# triangle.net
KiCad netlist of a schematic drawn in EAGLE
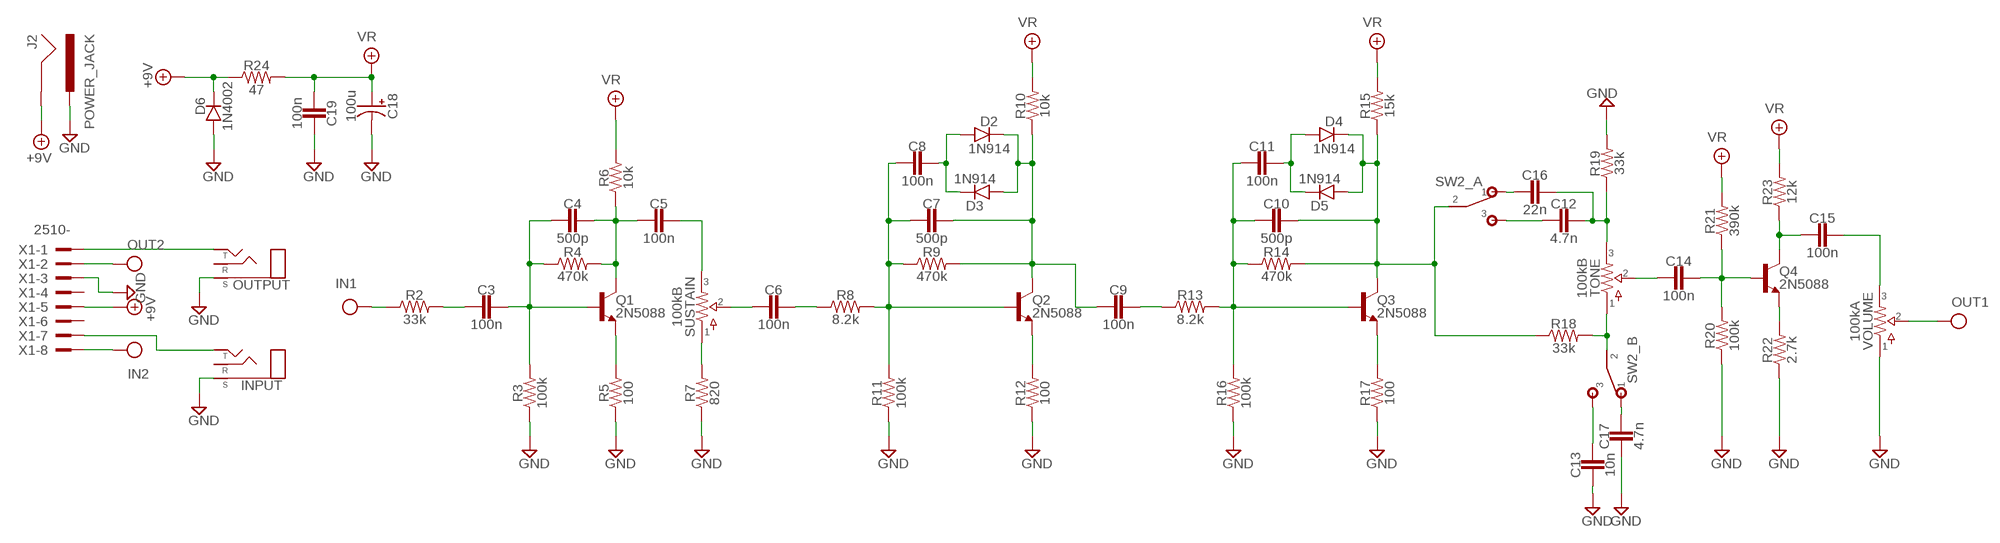
[diagram p0: schematic, sheet 1]

(export (version "E")
  (design (tool "Eeschema 10.0.6"))
  (components
    (comp (ref "C3")
      (value "100n")
      (footprint "eagle-import:BOX_SMALL")
      (libsource (lib "eagle-import") (part "CER/FILMBOX.1"))
    )
    (comp (ref "C4")
      (value "500p")
      (footprint "eagle-import:050X030_025_2")
      (libsource (lib "eagle-import") (part "CER/FILM2"))
    )
    (comp (ref "C5")
      (value "100n")
      (footprint "eagle-import:BOX_SMALL")
      (libsource (lib "eagle-import") (part "CER/FILMBOX.1"))
    )
    (comp (ref "C6")
      (value "100n")
      (footprint "eagle-import:BOX_SMALL")
      (libsource (lib "eagle-import") (part "CER/FILMBOX.1"))
    )
    (comp (ref "C7")
      (value "500p")
      (footprint "eagle-import:050X030_025_2")
      (libsource (lib "eagle-import") (part "CER/FILM2"))
    )
    (comp (ref "C8")
      (value "100n")
      (footprint "eagle-import:BOX_SMALL")
      (libsource (lib "eagle-import") (part "CER/FILMBOX.1"))
    )
    (comp (ref "C9")
      (value "100n")
      (footprint "eagle-import:BOX_SMALL")
      (libsource (lib "eagle-import") (part "CER/FILMBOX.1"))
    )
    (comp (ref "C10")
      (value "500p")
      (footprint "eagle-import:050X030_025_2")
      (libsource (lib "eagle-import") (part "CER/FILM2"))
    )
    (comp (ref "C11")
      (value "100n")
      (footprint "eagle-import:BOX_SMALL")
      (libsource (lib "eagle-import") (part "CER/FILMBOX.1"))
    )
    (comp (ref "C12")
      (value "4.7n")
      (footprint "eagle-import:BOX_SMALL")
      (libsource (lib "eagle-import") (part "CER/FILMBOX.1"))
    )
    (comp (ref "C13")
      (value "10n")
      (footprint "eagle-import:BOX_SMALL")
      (libsource (lib "eagle-import") (part "CER/FILMBOX.1"))
    )
    (comp (ref "C14")
      (value "100n")
      (footprint "eagle-import:BOX_SMALL")
      (libsource (lib "eagle-import") (part "CER/FILMBOX.1"))
    )
    (comp (ref "C15")
      (value "100n")
      (footprint "eagle-import:BOX_SMALL")
      (libsource (lib "eagle-import") (part "CER/FILMBOX.1"))
    )
    (comp (ref "C16")
      (value "22n")
      (footprint "eagle-import:BOX_SMALL")
      (libsource (lib "eagle-import") (part "CER/FILMBOX.1"))
    )
    (comp (ref "C17")
      (value "4.7n")
      (footprint "eagle-import:BOX_SMALL")
      (libsource (lib "eagle-import") (part "CER/FILMBOX.1"))
    )
    (comp (ref "C18")
      (value "100u")
      (footprint "eagle-import:050_020")
      (libsource (lib "eagle-import") (part "0500"))
    )
    (comp (ref "C19")
      (value "100n")
      (footprint "eagle-import:050X030_025_2")
      (libsource (lib "eagle-import") (part "CER/FILM2"))
    )
    (comp (ref "D2")
      (value "1N914")
      (footprint "eagle-import:DO35-2")
      (libsource (lib "eagle-import") (part "DO35.2"))
    )
    (comp (ref "D3")
      (value "1N914")
      (footprint "eagle-import:DO35-2")
      (libsource (lib "eagle-import") (part "DO35.2"))
    )
    (comp (ref "D4")
      (value "1N914")
      (footprint "eagle-import:DO35-2")
      (libsource (lib "eagle-import") (part "DO35.2"))
    )
    (comp (ref "D5")
      (value "1N914")
      (footprint "eagle-import:DO35-2")
      (libsource (lib "eagle-import") (part "DO35.2"))
    )
    (comp (ref "D6")
      (value "1N4002")
      (footprint "eagle-import:DO41-2")
      (libsource (lib "eagle-import") (part "DO41.2"))
    )
    (comp (ref "INPUT")
      (value "STEREONMJ")
      (footprint "eagle-import:NMJ6HCD2")
      (libsource (lib "eagle-import") (part "STEREONMJ"))
    )
    (comp (ref "J2")
      (value "POWER_JACK")
      (footprint "eagle-import:POWER_JACK_PTH")
      (libsource (lib "eagle-import") (part "POWER_JACK"))
    )
    (comp (ref "OUTPUT")
      (value "STEREONMJ")
      (footprint "eagle-import:NMJ6HCD2")
      (libsource (lib "eagle-import") (part "STEREONMJ"))
    )
    (comp (ref "Q1")
      (value "2N5088")
      (footprint "eagle-import:TO92-")
      (libsource (lib "eagle-import") (part "2N5088"))
    )
    (comp (ref "Q2")
      (value "2N5088")
      (footprint "eagle-import:TO92-")
      (libsource (lib "eagle-import") (part "2N5088"))
    )
    (comp (ref "Q3")
      (value "2N5088")
      (footprint "eagle-import:TO92-")
      (libsource (lib "eagle-import") (part "2N5088"))
    )
    (comp (ref "Q4")
      (value "2N5088")
      (footprint "eagle-import:TO92-")
      (libsource (lib "eagle-import") (part "2N5088"))
    )
    (comp (ref "R2")
      (value "33k")
      (footprint "eagle-import:R0207_3")
      (libsource (lib "eagle-import") (part "R_.3B"))
    )
    (comp (ref "R3")
      (value "100k")
      (footprint "eagle-import:R0207_3")
      (libsource (lib "eagle-import") (part "R_.3B"))
    )
    (comp (ref "R4")
      (value "470k")
      (footprint "eagle-import:R0207_3")
      (libsource (lib "eagle-import") (part "R_.3B"))
    )
    (comp (ref "R5")
      (value "100")
      (footprint "eagle-import:R0207_3")
      (libsource (lib "eagle-import") (part "R_.3B"))
    )
    (comp (ref "R6")
      (value "10k")
      (footprint "eagle-import:R0207_3")
      (libsource (lib "eagle-import") (part "R_.3B"))
    )
    (comp (ref "R7")
      (value "820")
      (footprint "eagle-import:R0207_3")
      (libsource (lib "eagle-import") (part "R_.3B"))
    )
    (comp (ref "R8")
      (value "8.2k")
      (footprint "eagle-import:R0207_3")
      (libsource (lib "eagle-import") (part "R_.3B"))
    )
    (comp (ref "R9")
      (value "470k")
      (footprint "eagle-import:R0207_3")
      (libsource (lib "eagle-import") (part "R_.3B"))
    )
    (comp (ref "R10")
      (value "10k")
      (footprint "eagle-import:R0207_3")
      (libsource (lib "eagle-import") (part "R_.3B"))
    )
    (comp (ref "R11")
      (value "100k")
      (footprint "eagle-import:R0207_3")
      (libsource (lib "eagle-import") (part "R_.3B"))
    )
    (comp (ref "R12")
      (value "100")
      (footprint "eagle-import:R0207_3")
      (libsource (lib "eagle-import") (part "R_.3B"))
    )
    (comp (ref "R13")
      (value "8.2k")
      (footprint "eagle-import:R0207_3")
      (libsource (lib "eagle-import") (part "R_.3B"))
    )
    (comp (ref "R14")
      (value "470k")
      (footprint "eagle-import:R0207_3")
      (libsource (lib "eagle-import") (part "R_.3B"))
    )
    (comp (ref "R15")
      (value "15k")
      (footprint "eagle-import:R0207_3")
      (libsource (lib "eagle-import") (part "R_.3B"))
    )
    (comp (ref "R16")
      (value "100k")
      (footprint "eagle-import:R0207_3")
      (libsource (lib "eagle-import") (part "R_.3B"))
    )
    (comp (ref "R17")
      (value "100")
      (footprint "eagle-import:R0207_3")
      (libsource (lib "eagle-import") (part "R_.3B"))
    )
    (comp (ref "R18")
      (value "33k")
      (footprint "eagle-import:R0207_3")
      (libsource (lib "eagle-import") (part "R_.3B"))
    )
    (comp (ref "R19")
      (value "33k")
      (footprint "eagle-import:R0207_3")
      (libsource (lib "eagle-import") (part "R_.3B"))
    )
    (comp (ref "R20")
      (value "100k")
      (footprint "eagle-import:R0207_3")
      (libsource (lib "eagle-import") (part "R_.3B"))
    )
    (comp (ref "R21")
      (value "390k")
      (footprint "eagle-import:R0207_3")
      (libsource (lib "eagle-import") (part "R_.3B"))
    )
    (comp (ref "R22")
      (value "2.7k")
      (footprint "eagle-import:R0207_3")
      (libsource (lib "eagle-import") (part "R_.3B"))
    )
    (comp (ref "R23")
      (value "12k")
      (footprint "eagle-import:R0207_3")
      (libsource (lib "eagle-import") (part "R_.3B"))
    )
    (comp (ref "R24")
      (value "47")
      (footprint "eagle-import:R0207_3")
      (libsource (lib "eagle-import") (part "R_.3B"))
    )
    (comp (ref "SUSTAIN")
      (value "100kB")
      (footprint "eagle-import:16MM")
      (libsource (lib "eagle-import") (part "POTS16MM"))
    )
    (comp (ref "SW2")
      (value "DPDT")
      (footprint "eagle-import:DPDT")
      (libsource (lib "eagle-import") (part "DPDT"))
    )
    (comp (ref "TONE")
      (value "100kB")
      (footprint "eagle-import:16MM")
      (libsource (lib "eagle-import") (part "POTS16MM"))
    )
    (comp (ref "VOLUME")
      (value "100kA")
      (footprint "eagle-import:16MM")
      (libsource (lib "eagle-import") (part "POTS16MM"))
    )
    (comp (ref "X1")
      (value "2510-")
      (footprint "eagle-import:PAK100_2500-10")
      (fields (field (name "MF") "3M") (field (name "MPN") "2510-6002UB"))
      (libsource (lib "eagle-import") (part "2510-"))
    )
  )
  (nets
    (net (code "1") (name "+9V") (class "Default")
      (node (ref "D6") (pin "C") (pinfunction "C_C") (pintype "passive"))
      (node (ref "J2") (pin "GND") (pinfunction "GND_GND") (pintype "bidirectional"))
      (node (ref "R24") (pin "1") (pinfunction "1_1") (pintype "passive"))
      (node (ref "X1") (pin "5") (pinfunction "KL_5") (pintype "passive"))
    )
    (net (code "2") (name "GND") (class "Default")
      (node (ref "C13") (pin "2") (pinfunction "2_2") (pintype "passive"))
      (node (ref "C17") (pin "2") (pinfunction "2_2") (pintype "passive"))
      (node (ref "C18") (pin "-") (pinfunction "-_-") (pintype "passive"))
      (node (ref "C19") (pin "1") (pinfunction "1_1") (pintype "passive"))
      (node (ref "D6") (pin "A") (pinfunction "A_A") (pintype "passive"))
      (node (ref "INPUT") (pin "S") (pinfunction "S_S") (pintype "passive"))
      (node (ref "J2") (pin "PWR") (pinfunction "PWR_PWR") (pintype "bidirectional"))
      (node (ref "OUTPUT") (pin "S") (pinfunction "S_S") (pintype "passive"))
      (node (ref "R11") (pin "1") (pinfunction "1_1") (pintype "passive"))
      (node (ref "R12") (pin "1") (pinfunction "1_1") (pintype "passive"))
      (node (ref "R16") (pin "1") (pinfunction "1_1") (pintype "passive"))
      (node (ref "R17") (pin "1") (pinfunction "1_1") (pintype "passive"))
      (node (ref "R19") (pin "2") (pinfunction "2_2") (pintype "passive"))
      (node (ref "R20") (pin "1") (pinfunction "1_1") (pintype "passive"))
      (node (ref "R22") (pin "1") (pinfunction "1_1") (pintype "passive"))
      (node (ref "R3") (pin "1") (pinfunction "1_1") (pintype "passive"))
      (node (ref "R5") (pin "1") (pinfunction "1_1") (pintype "passive"))
      (node (ref "R7") (pin "1") (pinfunction "1_1") (pintype "passive"))
      (node (ref "VOLUME") (pin "1") (pinfunction "1_1") (pintype "passive"))
      (node (ref "X1") (pin "3") (pinfunction "KL_3") (pintype "passive"))
    )
    (net (code "3") (name "IN") (class "Default")
      (node (ref "R2") (pin "1") (pinfunction "1_1") (pintype "passive"))
      (node (ref "X1") (pin "8") (pinfunction "KL_8") (pintype "passive"))
    )
    (net (code "4") (name "Net-(C3-Pad2)") (class "Default")
      (node (ref "C3") (pin "2") (pinfunction "2_2") (pintype "passive"))
      (node (ref "R2") (pin "2") (pinfunction "2_2") (pintype "passive"))
    )
    (net (code "5") (name "Net-(C5-Pad1)") (class "Default")
      (node (ref "C5") (pin "1") (pinfunction "1_1") (pintype "passive"))
      (node (ref "SUSTAIN") (pin "3") (pinfunction "3_3") (pintype "passive"))
    )
    (net (code "6") (name "Net-(C6-Pad1)") (class "Default")
      (node (ref "C6") (pin "1") (pinfunction "1_1") (pintype "passive"))
      (node (ref "R8") (pin "1") (pinfunction "1_1") (pintype "passive"))
    )
    (net (code "7") (name "Net-(C6-Pad2)") (class "Default")
      (node (ref "C6") (pin "2") (pinfunction "2_2") (pintype "passive"))
      (node (ref "SUSTAIN") (pin "2") (pinfunction "2_2") (pintype "passive"))
    )
    (net (code "8") (name "Net-(C8-Pad1)") (class "Default")
      (node (ref "C8") (pin "1") (pinfunction "1_1") (pintype "passive"))
      (node (ref "D2") (pin "A") (pinfunction "A_A") (pintype "passive"))
      (node (ref "D3") (pin "C") (pinfunction "C_C") (pintype "passive"))
    )
    (net (code "9") (name "Net-(C9-Pad1)") (class "Default")
      (node (ref "C9") (pin "1") (pinfunction "1_1") (pintype "passive"))
      (node (ref "R13") (pin "1") (pinfunction "1_1") (pintype "passive"))
    )
    (net (code "10") (name "Net-(C11-Pad1)") (class "Default")
      (node (ref "C11") (pin "1") (pinfunction "1_1") (pintype "passive"))
      (node (ref "D4") (pin "A") (pinfunction "A_A") (pintype "passive"))
      (node (ref "D5") (pin "C") (pinfunction "C_C") (pintype "passive"))
    )
    (net (code "11") (name "Net-(C12-Pad1)") (class "Default")
      (node (ref "C12") (pin "1") (pinfunction "1_1") (pintype "passive"))
      (node (ref "C16") (pin "1") (pinfunction "1_1") (pintype "passive"))
      (node (ref "R19") (pin "1") (pinfunction "1_1") (pintype "passive"))
      (node (ref "TONE") (pin "3") (pinfunction "3_3") (pintype "passive"))
    )
    (net (code "12") (name "Net-(C14-Pad2)") (class "Default")
      (node (ref "C14") (pin "2") (pinfunction "2_2") (pintype "passive"))
      (node (ref "TONE") (pin "2") (pinfunction "2_2") (pintype "passive"))
    )
    (net (code "13") (name "Net-(C15-Pad1)") (class "Default")
      (node (ref "C15") (pin "1") (pinfunction "1_1") (pintype "passive"))
      (node (ref "VOLUME") (pin "3") (pinfunction "3_3") (pintype "passive"))
    )
    (net (code "14") (name "Net-(Q1-B)") (class "Default")
      (node (ref "C3") (pin "1") (pinfunction "1_1") (pintype "passive"))
      (node (ref "C4") (pin "2") (pinfunction "2_2") (pintype "passive"))
      (node (ref "Q1") (pin "2") (pinfunction "B_2") (pintype "passive"))
      (node (ref "R3") (pin "2") (pinfunction "2_2") (pintype "passive"))
      (node (ref "R4") (pin "1") (pinfunction "1_1") (pintype "passive"))
    )
    (net (code "15") (name "Net-(Q1-C)") (class "Default")
      (node (ref "C4") (pin "1") (pinfunction "1_1") (pintype "passive"))
      (node (ref "C5") (pin "2") (pinfunction "2_2") (pintype "passive"))
      (node (ref "Q1") (pin "1") (pinfunction "C_1") (pintype "passive"))
      (node (ref "R4") (pin "2") (pinfunction "2_2") (pintype "passive"))
      (node (ref "R6") (pin "1") (pinfunction "1_1") (pintype "passive"))
    )
    (net (code "16") (name "Net-(Q1-E)") (class "Default")
      (node (ref "Q1") (pin "3") (pinfunction "E_3") (pintype "passive"))
      (node (ref "R5") (pin "2") (pinfunction "2_2") (pintype "passive"))
    )
    (net (code "17") (name "Net-(Q2-B)") (class "Default")
      (node (ref "C7") (pin "2") (pinfunction "2_2") (pintype "passive"))
      (node (ref "C8") (pin "2") (pinfunction "2_2") (pintype "passive"))
      (node (ref "Q2") (pin "2") (pinfunction "B_2") (pintype "passive"))
      (node (ref "R11") (pin "2") (pinfunction "2_2") (pintype "passive"))
      (node (ref "R8") (pin "2") (pinfunction "2_2") (pintype "passive"))
      (node (ref "R9") (pin "1") (pinfunction "1_1") (pintype "passive"))
    )
    (net (code "18") (name "Net-(Q2-C)") (class "Default")
      (node (ref "C7") (pin "1") (pinfunction "1_1") (pintype "passive"))
      (node (ref "C9") (pin "2") (pinfunction "2_2") (pintype "passive"))
      (node (ref "D2") (pin "C") (pinfunction "C_C") (pintype "passive"))
      (node (ref "D3") (pin "A") (pinfunction "A_A") (pintype "passive"))
      (node (ref "Q2") (pin "1") (pinfunction "C_1") (pintype "passive"))
      (node (ref "R10") (pin "1") (pinfunction "1_1") (pintype "passive"))
      (node (ref "R9") (pin "2") (pinfunction "2_2") (pintype "passive"))
    )
    (net (code "19") (name "Net-(Q2-E)") (class "Default")
      (node (ref "Q2") (pin "3") (pinfunction "E_3") (pintype "passive"))
      (node (ref "R12") (pin "2") (pinfunction "2_2") (pintype "passive"))
    )
    (net (code "20") (name "Net-(Q3-B)") (class "Default")
      (node (ref "C10") (pin "2") (pinfunction "2_2") (pintype "passive"))
      (node (ref "C11") (pin "2") (pinfunction "2_2") (pintype "passive"))
      (node (ref "Q3") (pin "2") (pinfunction "B_2") (pintype "passive"))
      (node (ref "R13") (pin "2") (pinfunction "2_2") (pintype "passive"))
      (node (ref "R14") (pin "1") (pinfunction "1_1") (pintype "passive"))
      (node (ref "R16") (pin "2") (pinfunction "2_2") (pintype "passive"))
    )
    (net (code "21") (name "Net-(Q3-C)") (class "Default")
      (node (ref "C10") (pin "1") (pinfunction "1_1") (pintype "passive"))
      (node (ref "D4") (pin "C") (pinfunction "C_C") (pintype "passive"))
      (node (ref "D5") (pin "A") (pinfunction "A_A") (pintype "passive"))
      (node (ref "Q3") (pin "1") (pinfunction "C_1") (pintype "passive"))
      (node (ref "R14") (pin "2") (pinfunction "2_2") (pintype "passive"))
      (node (ref "R15") (pin "1") (pinfunction "1_1") (pintype "passive"))
      (node (ref "R18") (pin "1") (pinfunction "1_1") (pintype "passive"))
      (node (ref "SW2") (pin "A2") (pinfunction "2_A2") (pintype "passive"))
    )
    (net (code "22") (name "Net-(Q3-E)") (class "Default")
      (node (ref "Q3") (pin "3") (pinfunction "E_3") (pintype "passive"))
      (node (ref "R17") (pin "2") (pinfunction "2_2") (pintype "passive"))
    )
    (net (code "23") (name "Net-(Q4-B)") (class "Default")
      (node (ref "C14") (pin "1") (pinfunction "1_1") (pintype "passive"))
      (node (ref "Q4") (pin "2") (pinfunction "B_2") (pintype "passive"))
      (node (ref "R20") (pin "2") (pinfunction "2_2") (pintype "passive"))
      (node (ref "R21") (pin "1") (pinfunction "1_1") (pintype "passive"))
    )
    (net (code "24") (name "Net-(Q4-C)") (class "Default")
      (node (ref "C15") (pin "2") (pinfunction "2_2") (pintype "passive"))
      (node (ref "Q4") (pin "1") (pinfunction "C_1") (pintype "passive"))
      (node (ref "R23") (pin "1") (pinfunction "1_1") (pintype "passive"))
    )
    (net (code "25") (name "Net-(Q4-E)") (class "Default")
      (node (ref "Q4") (pin "3") (pinfunction "E_3") (pintype "passive"))
      (node (ref "R22") (pin "2") (pinfunction "2_2") (pintype "passive"))
    )
    (net (code "26") (name "Net-(R7-Pad2)") (class "Default")
      (node (ref "R7") (pin "2") (pinfunction "2_2") (pintype "passive"))
      (node (ref "SUSTAIN") (pin "1") (pinfunction "1_1") (pintype "passive"))
    )
    (net (code "27") (name "Net-(SW2A-1)") (class "Default")
      (node (ref "C16") (pin "2") (pinfunction "2_2") (pintype "passive"))
      (node (ref "SW2") (pin "A1") (pinfunction "1_A1") (pintype "passive"))
    )
    (net (code "28") (name "Net-(SW2A-3)") (class "Default")
      (node (ref "C12") (pin "2") (pinfunction "2_2") (pintype "passive"))
      (node (ref "SW2") (pin "A3") (pinfunction "3_A3") (pintype "passive"))
    )
    (net (code "29") (name "Net-(SW2B-1)") (class "Default")
      (node (ref "C17") (pin "1") (pinfunction "1_1") (pintype "passive"))
      (node (ref "SW2") (pin "B1") (pinfunction "1_B1") (pintype "passive"))
    )
    (net (code "30") (name "Net-(SW2B-2)") (class "Default")
      (node (ref "R18") (pin "2") (pinfunction "2_2") (pintype "passive"))
      (node (ref "SW2") (pin "B2") (pinfunction "2_B2") (pintype "passive"))
      (node (ref "TONE") (pin "1") (pinfunction "1_1") (pintype "passive"))
    )
    (net (code "31") (name "Net-(SW2B-3)") (class "Default")
      (node (ref "C13") (pin "1") (pinfunction "1_1") (pintype "passive"))
      (node (ref "SW2") (pin "B3") (pinfunction "3_B3") (pintype "passive"))
    )
    (net (code "32") (name "Net-(X1A-KL)") (class "Default")
      (node (ref "OUTPUT") (pin "T") (pinfunction "T_T") (pintype "passive"))
      (node (ref "X1") (pin "1") (pinfunction "KL_1") (pintype "passive"))
    )
    (net (code "33") (name "Net-(X1G-KL)") (class "Default")
      (node (ref "INPUT") (pin "T") (pinfunction "T_T") (pintype "passive"))
      (node (ref "X1") (pin "7") (pinfunction "KL_7") (pintype "passive"))
    )
    (net (code "34") (name "OUT") (class "Default")
      (node (ref "VOLUME") (pin "2") (pinfunction "2_2") (pintype "passive"))
      (node (ref "X1") (pin "2") (pinfunction "KL_2") (pintype "passive"))
    )
    (net (code "35") (name "VR") (class "Default")
      (node (ref "C18") (pin "+") (pinfunction "+_+") (pintype "passive"))
      (node (ref "C19") (pin "2") (pinfunction "2_2") (pintype "passive"))
      (node (ref "R10") (pin "2") (pinfunction "2_2") (pintype "passive"))
      (node (ref "R15") (pin "2") (pinfunction "2_2") (pintype "passive"))
      (node (ref "R21") (pin "2") (pinfunction "2_2") (pintype "passive"))
      (node (ref "R23") (pin "2") (pinfunction "2_2") (pintype "passive"))
      (node (ref "R24") (pin "2") (pinfunction "2_2") (pintype "passive"))
      (node (ref "R6") (pin "2") (pinfunction "2_2") (pintype "passive"))
    )
    (net (code "36") (name "unconnected-(INPUT-PadR)") (class "Default")
      (node (ref "INPUT") (pin "R") (pinfunction "R_R") (pintype "passive"))
    )
    (net (code "37") (name "unconnected-(OUTPUT-PadR)") (class "Default")
      (node (ref "OUTPUT") (pin "R") (pinfunction "R_R") (pintype "passive"))
    )
    (net (code "38") (name "unconnected-(X1D-KL-Pad4)") (class "Default")
      (node (ref "X1") (pin "4") (pinfunction "KL_4") (pintype "passive"))
    )
    (net (code "39") (name "unconnected-(X1F-KL-Pad6)") (class "Default")
      (node (ref "X1") (pin "6") (pinfunction "KL_6") (pintype "passive"))
    )
  )
)
